# Analog_Light_Project_Schematic_v1.net
KiCad netlist of a schematic drawn in EAGLE
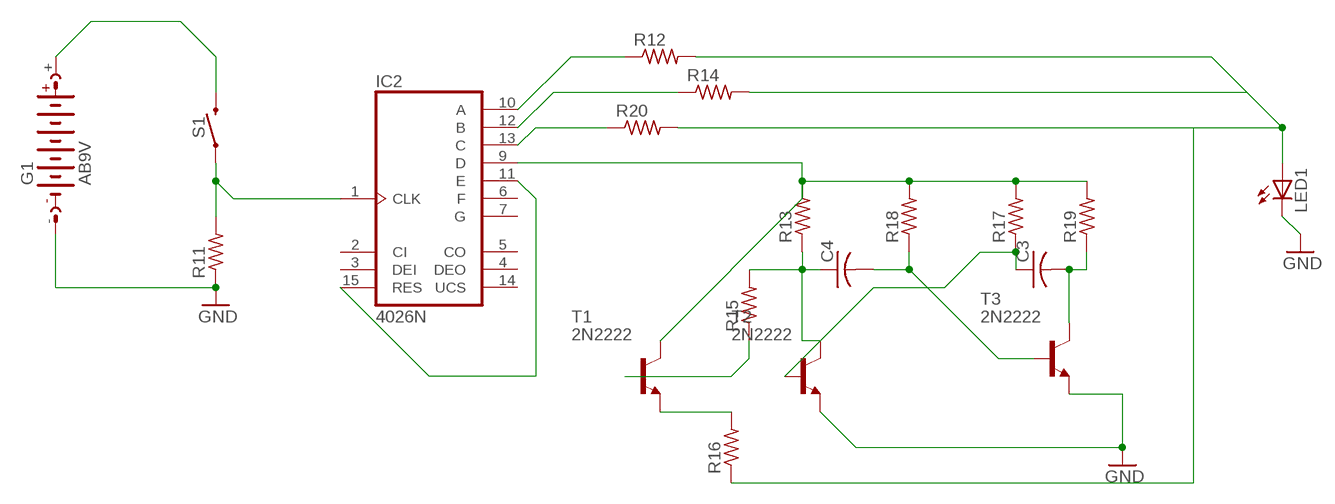
[diagram p0: schematic, sheet 1]

(export (version "E")
  (design (tool "Eeschema 10.0.6"))
  (components
    (comp (ref "C3")
      (value "C-USC0805")
      (footprint "eagle-import:C0805")
      (libsource (lib "eagle-import") (part "C-USC0805"))
    )
    (comp (ref "C4")
      (value "C-USC0805")
      (footprint "eagle-import:C0805")
      (libsource (lib "eagle-import") (part "C-USC0805"))
    )
    (comp (ref "G1")
      (value "AB9V")
      (footprint "eagle-import:AB9V")
      (libsource (lib "eagle-import") (part "AB9V"))
    )
    (comp (ref "IC2")
      (value "4026N")
      (footprint "eagle-import:DIL16")
      (libsource (lib "eagle-import") (part "4026N"))
    )
    (comp (ref "LED1")
      (value "LED5MM")
      (footprint "eagle-import:LED5MM")
      (libsource (lib "eagle-import") (part "LED5MM"))
    )
    (comp (ref "R11")
      (value "R-US_M0805")
      (footprint "eagle-import:M0805")
      (libsource (lib "eagle-import") (part "R-US_M0805"))
    )
    (comp (ref "R12")
      (value "R-US_M0805")
      (footprint "eagle-import:M0805")
      (libsource (lib "eagle-import") (part "R-US_M0805"))
    )
    (comp (ref "R13")
      (value "R-US_M0805")
      (footprint "eagle-import:M0805")
      (libsource (lib "eagle-import") (part "R-US_M0805"))
    )
    (comp (ref "R14")
      (value "R-US_M0805")
      (footprint "eagle-import:M0805")
      (libsource (lib "eagle-import") (part "R-US_M0805"))
    )
    (comp (ref "R15")
      (value "R-US_M0805")
      (footprint "eagle-import:M0805")
      (libsource (lib "eagle-import") (part "R-US_M0805"))
    )
    (comp (ref "R16")
      (value "R-US_M0805")
      (footprint "eagle-import:M0805")
      (libsource (lib "eagle-import") (part "R-US_M0805"))
    )
    (comp (ref "R17")
      (value "R-US_M0805")
      (footprint "eagle-import:M0805")
      (libsource (lib "eagle-import") (part "R-US_M0805"))
    )
    (comp (ref "R18")
      (value "R-US_M0805")
      (footprint "eagle-import:M0805")
      (libsource (lib "eagle-import") (part "R-US_M0805"))
    )
    (comp (ref "R19")
      (value "R-US_M0805")
      (footprint "eagle-import:M0805")
      (libsource (lib "eagle-import") (part "R-US_M0805"))
    )
    (comp (ref "R20")
      (value "R-US_M0805")
      (footprint "eagle-import:M0805")
      (libsource (lib "eagle-import") (part "R-US_M0805"))
    )
    (comp (ref "S1")
      (value "MOMENTARY-SWITCH-SPST-PTH-6.0MM-KIT")
      (footprint "eagle-import:TACTILE_SWITCH_PTH_6.0MM_KIT")
      (libsource (lib "eagle-import") (part "MOMENTARY-SWITCH-SPST-PTH-6.0MM-KIT"))
    )
    (comp (ref "T1")
      (value "2N2222")
      (footprint "eagle-import:TO92-EBC-OVAL")
      (libsource (lib "eagle-import") (part "2N2222"))
    )
    (comp (ref "T2")
      (value "2N2222")
      (footprint "eagle-import:TO92-EBC-OVAL")
      (libsource (lib "eagle-import") (part "2N2222"))
    )
    (comp (ref "T3")
      (value "2N2222")
      (footprint "eagle-import:TO92-EBC-OVAL")
      (libsource (lib "eagle-import") (part "2N2222"))
    )
  )
  (nets
    (net (code "1") (name "GND") (class "Default")
      (node (ref "G1") (pin "-") (pinfunction "-_-") (pintype "passive"))
      (node (ref "LED1") (pin "K") (pinfunction "C_K") (pintype "passive"))
      (node (ref "R11") (pin "1") (pinfunction "1_1") (pintype "passive"))
      (node (ref "T2") (pin "E") (pinfunction "E_E") (pintype "passive"))
      (node (ref "T3") (pin "E") (pinfunction "E_E") (pintype "passive"))
    )
    (net (code "2") (name "Net-(C3-Pad1)") (class "Default")
      (node (ref "C3") (pin "1") (pinfunction "1_1") (pintype "passive"))
      (node (ref "R17") (pin "1") (pinfunction "1_1") (pintype "passive"))
      (node (ref "T2") (pin "B") (pinfunction "B_B") (pintype "passive"))
    )
    (net (code "3") (name "Net-(C3-Pad2)") (class "Default")
      (node (ref "C3") (pin "2") (pinfunction "2_2") (pintype "passive"))
      (node (ref "R19") (pin "1") (pinfunction "1_1") (pintype "passive"))
      (node (ref "T3") (pin "C") (pinfunction "C_C") (pintype "passive"))
    )
    (net (code "4") (name "Net-(C4-Pad1)") (class "Default")
      (node (ref "C4") (pin "1") (pinfunction "1_1") (pintype "passive"))
      (node (ref "R13") (pin "1") (pinfunction "1_1") (pintype "passive"))
      (node (ref "R15") (pin "2") (pinfunction "2_2") (pintype "passive"))
      (node (ref "T2") (pin "C") (pinfunction "C_C") (pintype "passive"))
    )
    (net (code "5") (name "Net-(C4-Pad2)") (class "Default")
      (node (ref "C4") (pin "2") (pinfunction "2_2") (pintype "passive"))
      (node (ref "R18") (pin "1") (pinfunction "1_1") (pintype "passive"))
      (node (ref "T3") (pin "B") (pinfunction "B_B") (pintype "passive"))
    )
    (net (code "6") (name "Net-(IC2A-A)") (class "Default")
      (node (ref "IC2") (pin "10") (pinfunction "A_10") (pintype "output"))
      (node (ref "R12") (pin "1") (pinfunction "1_1") (pintype "passive"))
    )
    (net (code "7") (name "Net-(IC2A-B)") (class "Default")
      (node (ref "IC2") (pin "12") (pinfunction "B_12") (pintype "output"))
      (node (ref "R14") (pin "1") (pinfunction "1_1") (pintype "passive"))
    )
    (net (code "8") (name "Net-(IC2A-C)") (class "Default")
      (node (ref "IC2") (pin "13") (pinfunction "C_13") (pintype "output"))
      (node (ref "R20") (pin "1") (pinfunction "1_1") (pintype "passive"))
    )
    (net (code "9") (name "Net-(IC2A-CLK)") (class "Default")
      (node (ref "IC2") (pin "1") (pinfunction "CLK_1") (pintype "input"))
      (node (ref "R11") (pin "2") (pinfunction "2_2") (pintype "passive"))
      (node (ref "S1") (pin "1") (pinfunction "1_1") (pintype "passive"))
    )
    (net (code "10") (name "Net-(IC2A-D)") (class "Default")
      (node (ref "IC2") (pin "9") (pinfunction "D_9") (pintype "output"))
      (node (ref "R13") (pin "2") (pinfunction "2_2") (pintype "passive"))
      (node (ref "R17") (pin "2") (pinfunction "2_2") (pintype "passive"))
      (node (ref "R18") (pin "2") (pinfunction "2_2") (pintype "passive"))
      (node (ref "R19") (pin "2") (pinfunction "2_2") (pintype "passive"))
      (node (ref "T1") (pin "C") (pinfunction "C_C") (pintype "passive"))
    )
    (net (code "11") (name "Net-(IC2A-E)") (class "Default")
      (node (ref "IC2") (pin "11") (pinfunction "E_11") (pintype "output"))
      (node (ref "IC2") (pin "15") (pinfunction "RES_15") (pintype "input"))
    )
    (net (code "12") (name "Net-(LED1-PadA)") (class "Default")
      (node (ref "LED1") (pin "A") (pinfunction "A_A") (pintype "passive"))
      (node (ref "R12") (pin "2") (pinfunction "2_2") (pintype "passive"))
      (node (ref "R14") (pin "2") (pinfunction "2_2") (pintype "passive"))
      (node (ref "R16") (pin "1") (pinfunction "1_1") (pintype "passive"))
      (node (ref "R20") (pin "2") (pinfunction "2_2") (pintype "passive"))
    )
    (net (code "13") (name "Net-(R15-Pad1)") (class "Default")
      (node (ref "R15") (pin "1") (pinfunction "1_1") (pintype "passive"))
      (node (ref "T1") (pin "B") (pinfunction "B_B") (pintype "passive"))
    )
    (net (code "14") (name "Net-(R16-Pad2)") (class "Default")
      (node (ref "R16") (pin "2") (pinfunction "2_2") (pintype "passive"))
      (node (ref "T1") (pin "E") (pinfunction "E_E") (pintype "passive"))
    )
    (net (code "15") (name "Net-(S1-2)") (class "Default")
      (node (ref "G1") (pin "+") (pinfunction "+_+") (pintype "passive"))
      (node (ref "S1") (pin "3") (pinfunction "2_3") (pintype "passive"))
    )
    (net (code "16") (name "unconnected-(IC2A-CI-Pad2)") (class "Default")
      (node (ref "IC2") (pin "2") (pinfunction "CI_2") (pintype "input"))
    )
    (net (code "17") (name "unconnected-(IC2A-CO-Pad5)") (class "Default")
      (node (ref "IC2") (pin "5") (pinfunction "CO_5") (pintype "output"))
    )
    (net (code "18") (name "unconnected-(IC2A-DEI-Pad3)") (class "Default")
      (node (ref "IC2") (pin "3") (pinfunction "DEI_3") (pintype "input"))
    )
    (net (code "19") (name "unconnected-(IC2A-DEO-Pad4)") (class "Default")
      (node (ref "IC2") (pin "4") (pinfunction "DEO_4") (pintype "output"))
    )
    (net (code "20") (name "unconnected-(IC2A-F-Pad6)") (class "Default")
      (node (ref "IC2") (pin "6") (pinfunction "F_6") (pintype "output"))
    )
    (net (code "21") (name "unconnected-(IC2A-G-Pad7)") (class "Default")
      (node (ref "IC2") (pin "7") (pinfunction "G_7") (pintype "output"))
    )
    (net (code "22") (name "unconnected-(IC2A-UCS-Pad14)") (class "Default")
      (node (ref "IC2") (pin "14") (pinfunction "UCS_14") (pintype "output"))
    )
  )
)
